# Fall_Analyzer_Circuit.net
KiCad netlist of a schematic drawn in EAGLE
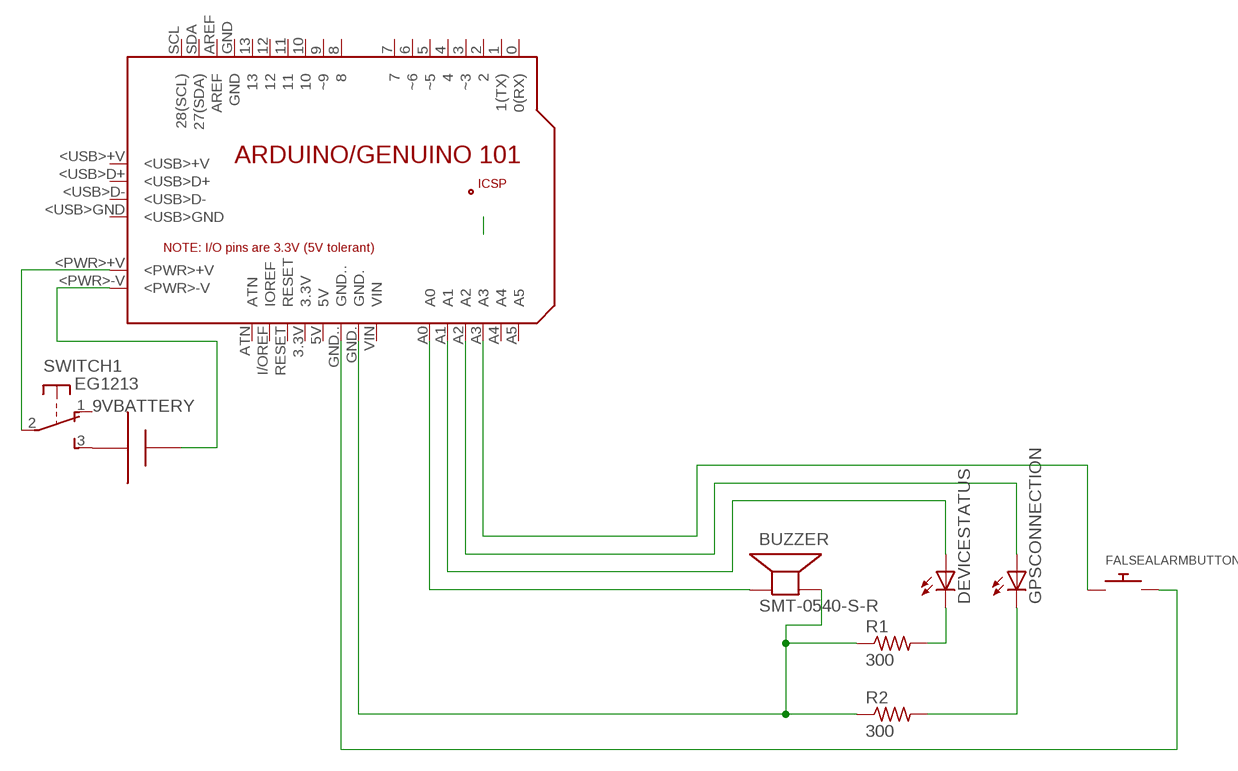
[diagram p0: schematic, sheet 1]

(export (version "E")
  (design (tool "Eeschema 10.0.6"))
  (components
    (comp (ref "9VBATTERY")
      (value "AAA")
      (footprint "eagle-import:12BH412")
      (libsource (lib "eagle-import") (part "AAA"))
    )
    (comp (ref "BUZZER")
      (value "SMT-0540-S-R")
      (footprint "eagle-import:SMT-0540-S-R")
      (libsource (lib "eagle-import") (part "SMT-0540-S-R"))
    )
    (comp (ref "DEVICESTATUS")
      (value "LED3MM")
      (footprint "eagle-import:LED3MM")
      (libsource (lib "eagle-import") (part "LED3MM"))
    )
    (comp (ref "FALSEALARMBUTTON")
      (value "SWITCH_PUSHBUTTONSOFTTOUCHSMD_SJ")
      (footprint "eagle-import:PUSHBUTTON_SMD_SJ")
      (libsource (lib "eagle-import") (part "SWITCH_PUSHBUTTONSOFTTOUCHSMD_SJ"))
    )
    (comp (ref "GPSCONNECTION")
      (value "LED3MM")
      (footprint "eagle-import:LED3MM")
      (libsource (lib "eagle-import") (part "LED3MM"))
    )
    (comp (ref "PCB1")
      (value "ARDUINO_101")
      (footprint "eagle-import:ARDUINO_101")
      (libsource (lib "eagle-import") (part "ARDUINO_101"))
    )
    (comp (ref "R1")
      (value "300")
      (footprint "eagle-import:0204_7")
      (libsource (lib "eagle-import") (part "R-US_0204/7"))
    )
    (comp (ref "R2")
      (value "300")
      (footprint "eagle-import:0204_7")
      (libsource (lib "eagle-import") (part "R-US_0204/7"))
    )
    (comp (ref "SWITCH")
      (value "EG1213")
      (footprint "eagle-import:EG1213")
      (libsource (lib "eagle-import") (part "EG1213"))
    )
  )
  (nets
    (net (code "1") (name "Net-(9VBATTERY-Pad+)") (class "Default")
      (node (ref "9VBATTERY") (pin "+") (pinfunction "+_+") (pintype "bidirectional"))
      (node (ref "PCB1") (pin "<PWR>-V") (pinfunction "<PWR>-V_<PWR>-V") (pintype "bidirectional"))
    )
    (net (code "2") (name "Net-(BUZZER-+)") (class "Default")
      (node (ref "BUZZER") (pin "-") (pinfunction "+_-") (pintype "passive"))
      (node (ref "PCB1") (pin "A0") (pinfunction "A0_A0") (pintype "bidirectional"))
    )
    (net (code "3") (name "Net-(BUZZER--)") (class "Default")
      (node (ref "BUZZER") (pin "+") (pinfunction "-_+") (pintype "passive"))
      (node (ref "PCB1") (pin "GND.") (pinfunction "GND._GND.") (pintype "bidirectional"))
      (node (ref "R1") (pin "1") (pinfunction "1_1") (pintype "passive"))
      (node (ref "R2") (pin "1") (pinfunction "1_1") (pintype "passive"))
    )
    (net (code "4") (name "Net-(DEVICESTATUS-C)") (class "Default")
      (node (ref "DEVICESTATUS") (pin "K") (pinfunction "C_K") (pintype "passive"))
      (node (ref "R1") (pin "2") (pinfunction "2_2") (pintype "passive"))
    )
    (net (code "5") (name "Net-(DEVICESTATUS-PadA)") (class "Default")
      (node (ref "DEVICESTATUS") (pin "A") (pinfunction "A_A") (pintype "passive"))
      (node (ref "PCB1") (pin "A1") (pinfunction "A1_A1") (pintype "bidirectional"))
    )
    (net (code "6") (name "Net-(FALSEALARMBUTTON-PadP$1)") (class "Default")
      (node (ref "FALSEALARMBUTTON") (pin "P$1") (pinfunction "P$1_P$1") (pintype "passive"))
      (node (ref "PCB1") (pin "A3") (pinfunction "A3_A3") (pintype "bidirectional"))
    )
    (net (code "7") (name "Net-(FALSEALARMBUTTON-PadP$2)") (class "Default")
      (node (ref "FALSEALARMBUTTON") (pin "P$2") (pinfunction "P$2_P$2") (pintype "passive"))
      (node (ref "PCB1") (pin "GND..") (pinfunction "GND.._GND..") (pintype "bidirectional"))
    )
    (net (code "8") (name "Net-(GPSCONNECTION-C)") (class "Default")
      (node (ref "GPSCONNECTION") (pin "K") (pinfunction "C_K") (pintype "passive"))
      (node (ref "R2") (pin "2") (pinfunction "2_2") (pintype "passive"))
    )
    (net (code "9") (name "Net-(GPSCONNECTION-PadA)") (class "Default")
      (node (ref "GPSCONNECTION") (pin "A") (pinfunction "A_A") (pintype "passive"))
      (node (ref "PCB1") (pin "A2") (pinfunction "A2_A2") (pintype "bidirectional"))
    )
    (net (code "10") (name "Net-(PCB1-PadRESET.)") (class "Default")
      (node (ref "PCB1") (pin "RESET.") (pinfunction "RESET._RESET.") (pintype "bidirectional"))
      (node (ref "PCB1") (pin "SCK") (pinfunction "SCK_SCK") (pintype "bidirectional"))
    )
    (net (code "11") (name "Net-(SWITCHA-P)") (class "Default")
      (node (ref "PCB1") (pin "<PWR>+V") (pinfunction "<PWR>+V_<PWR>+V") (pintype "bidirectional"))
      (node (ref "SWITCH") (pin "2") (pinfunction "P_2") (pintype "passive"))
    )
    (net (code "12") (name "Net-(SWITCHA-S)") (class "Default")
      (node (ref "9VBATTERY") (pin "-") (pinfunction "-_-") (pintype "bidirectional"))
      (node (ref "SWITCH") (pin "3") (pinfunction "S_3") (pintype "passive"))
    )
    (net (code "13") (name "unconnected-(PCB1-0(RX)-Pad0)") (class "Default")
      (node (ref "PCB1") (pin "0") (pinfunction "0(RX)_0") (pintype "bidirectional"))
    )
    (net (code "14") (name "unconnected-(PCB1-1(TX)-Pad1)") (class "Default")
      (node (ref "PCB1") (pin "1") (pinfunction "1(TX)_1") (pintype "bidirectional"))
    )
    (net (code "15") (name "unconnected-(PCB1-27(SDA)-PadSDA)") (class "Default")
      (node (ref "PCB1") (pin "SDA") (pinfunction "27(SDA)_SDA") (pintype "bidirectional"))
    )
    (net (code "16") (name "unconnected-(PCB1-28(SCL)-PadSCL)") (class "Default")
      (node (ref "PCB1") (pin "SCL") (pinfunction "28(SCL)_SCL") (pintype "bidirectional"))
    )
    (net (code "17") (name "unconnected-(PCB1-IOREF-PadI{slash}OREF)") (class "Default")
      (node (ref "PCB1") (pin "I/OREF") (pinfunction "IOREF_I/OREF") (pintype "bidirectional"))
    )
    (net (code "18") (name "unconnected-(PCB1-Pad+5V)") (class "Default")
      (node (ref "PCB1") (pin "+5V") (pinfunction "+5V_+5V") (pintype "bidirectional"))
    )
    (net (code "19") (name "unconnected-(PCB1-Pad2)") (class "Default")
      (node (ref "PCB1") (pin "2") (pinfunction "2_2") (pintype "bidirectional"))
    )
    (net (code "20") (name "unconnected-(PCB1-Pad3.3V)") (class "Default")
      (node (ref "PCB1") (pin "3.3V") (pinfunction "3.3V_3.3V") (pintype "bidirectional"))
    )
    (net (code "21") (name "unconnected-(PCB1-Pad4)") (class "Default")
      (node (ref "PCB1") (pin "4") (pinfunction "4_4") (pintype "bidirectional"))
    )
    (net (code "22") (name "unconnected-(PCB1-Pad5V)") (class "Default")
      (node (ref "PCB1") (pin "5V") (pinfunction "5V_5V") (pintype "bidirectional"))
    )
    (net (code "23") (name "unconnected-(PCB1-Pad7)") (class "Default")
      (node (ref "PCB1") (pin "7") (pinfunction "7_7") (pintype "bidirectional"))
    )
    (net (code "24") (name "unconnected-(PCB1-Pad8)") (class "Default")
      (node (ref "PCB1") (pin "8") (pinfunction "8_8") (pintype "bidirectional"))
    )
    (net (code "25") (name "unconnected-(PCB1-Pad10)") (class "Default")
      (node (ref "PCB1") (pin "10") (pinfunction "10_10") (pintype "bidirectional"))
    )
    (net (code "26") (name "unconnected-(PCB1-Pad11)") (class "Default")
      (node (ref "PCB1") (pin "11") (pinfunction "11_11") (pintype "bidirectional"))
    )
    (net (code "27") (name "unconnected-(PCB1-Pad12)") (class "Default")
      (node (ref "PCB1") (pin "12") (pinfunction "12_12") (pintype "bidirectional"))
    )
    (net (code "28") (name "unconnected-(PCB1-Pad13)") (class "Default")
      (node (ref "PCB1") (pin "13") (pinfunction "13_13") (pintype "bidirectional"))
    )
    (net (code "29") (name "unconnected-(PCB1-Pad<USB>+V)") (class "Default")
      (node (ref "PCB1") (pin "<USB>+V") (pinfunction "<USB>+V_<USB>+V") (pintype "bidirectional"))
    )
    (net (code "30") (name "unconnected-(PCB1-Pad<USB>D+)") (class "Default")
      (node (ref "PCB1") (pin "<USB>D+") (pinfunction "<USB>D+_<USB>D+") (pintype "bidirectional"))
    )
    (net (code "31") (name "unconnected-(PCB1-Pad<USB>D-)") (class "Default")
      (node (ref "PCB1") (pin "<USB>D-") (pinfunction "<USB>D-_<USB>D-") (pintype "bidirectional"))
    )
    (net (code "32") (name "unconnected-(PCB1-Pad<USB>GND)") (class "Default")
      (node (ref "PCB1") (pin "<USB>GND") (pinfunction "<USB>GND_<USB>GND") (pintype "bidirectional"))
    )
    (net (code "33") (name "unconnected-(PCB1-PadA4)") (class "Default")
      (node (ref "PCB1") (pin "A4") (pinfunction "A4_A4") (pintype "bidirectional"))
    )
    (net (code "34") (name "unconnected-(PCB1-PadA5)") (class "Default")
      (node (ref "PCB1") (pin "A5") (pinfunction "A5_A5") (pintype "bidirectional"))
    )
    (net (code "35") (name "unconnected-(PCB1-PadAREF)") (class "Default")
      (node (ref "PCB1") (pin "AREF") (pinfunction "AREF_AREF") (pintype "bidirectional"))
    )
    (net (code "36") (name "unconnected-(PCB1-PadATN)") (class "Default")
      (node (ref "PCB1") (pin "ATN") (pinfunction "ATN_ATN") (pintype "bidirectional"))
    )
    (net (code "37") (name "unconnected-(PCB1-PadGND)") (class "Default")
      (node (ref "PCB1") (pin "GND") (pinfunction "GND_GND") (pintype "bidirectional"))
    )
    (net (code "38") (name "unconnected-(PCB1-PadGND_)") (class "Default")
      (node (ref "PCB1") (pin "GND_") (pinfunction "GND__GND_") (pintype "bidirectional"))
    )
    (net (code "39") (name "unconnected-(PCB1-PadMISO)") (class "Default")
      (node (ref "PCB1") (pin "MISO") (pinfunction "MISO_MISO") (pintype "bidirectional"))
    )
    (net (code "40") (name "unconnected-(PCB1-PadMOSI)") (class "Default")
      (node (ref "PCB1") (pin "MOSI") (pinfunction "MOSI_MOSI") (pintype "bidirectional"))
    )
    (net (code "41") (name "unconnected-(PCB1-PadRESET)") (class "Default")
      (node (ref "PCB1") (pin "RESET") (pinfunction "RESET_RESET") (pintype "bidirectional"))
    )
    (net (code "42") (name "unconnected-(PCB1-PadVIN)") (class "Default")
      (node (ref "PCB1") (pin "VIN") (pinfunction "VIN_VIN") (pintype "bidirectional"))
    )
    (net (code "43") (name "unconnected-(PCB1-~{3}-Pad3)") (class "Default")
      (node (ref "PCB1") (pin "3") (pinfunction "~{3}_3") (pintype "bidirectional"))
    )
    (net (code "44") (name "unconnected-(PCB1-~{5}-Pad5)") (class "Default")
      (node (ref "PCB1") (pin "5") (pinfunction "~{5}_5") (pintype "bidirectional"))
    )
    (net (code "45") (name "unconnected-(PCB1-~{6}-Pad6)") (class "Default")
      (node (ref "PCB1") (pin "6") (pinfunction "~{6}_6") (pintype "bidirectional"))
    )
    (net (code "46") (name "unconnected-(PCB1-~{9}-Pad9)") (class "Default")
      (node (ref "PCB1") (pin "9") (pinfunction "~{9}_9") (pintype "bidirectional"))
    )
    (net (code "47") (name "unconnected-(SWITCHA-O-Pad1)") (class "Default")
      (node (ref "SWITCH") (pin "1") (pinfunction "O_1") (pintype "passive"))
    )
  )
)
